# 16F1619segadc.net
KiCad netlist of a schematic drawn in EAGLE
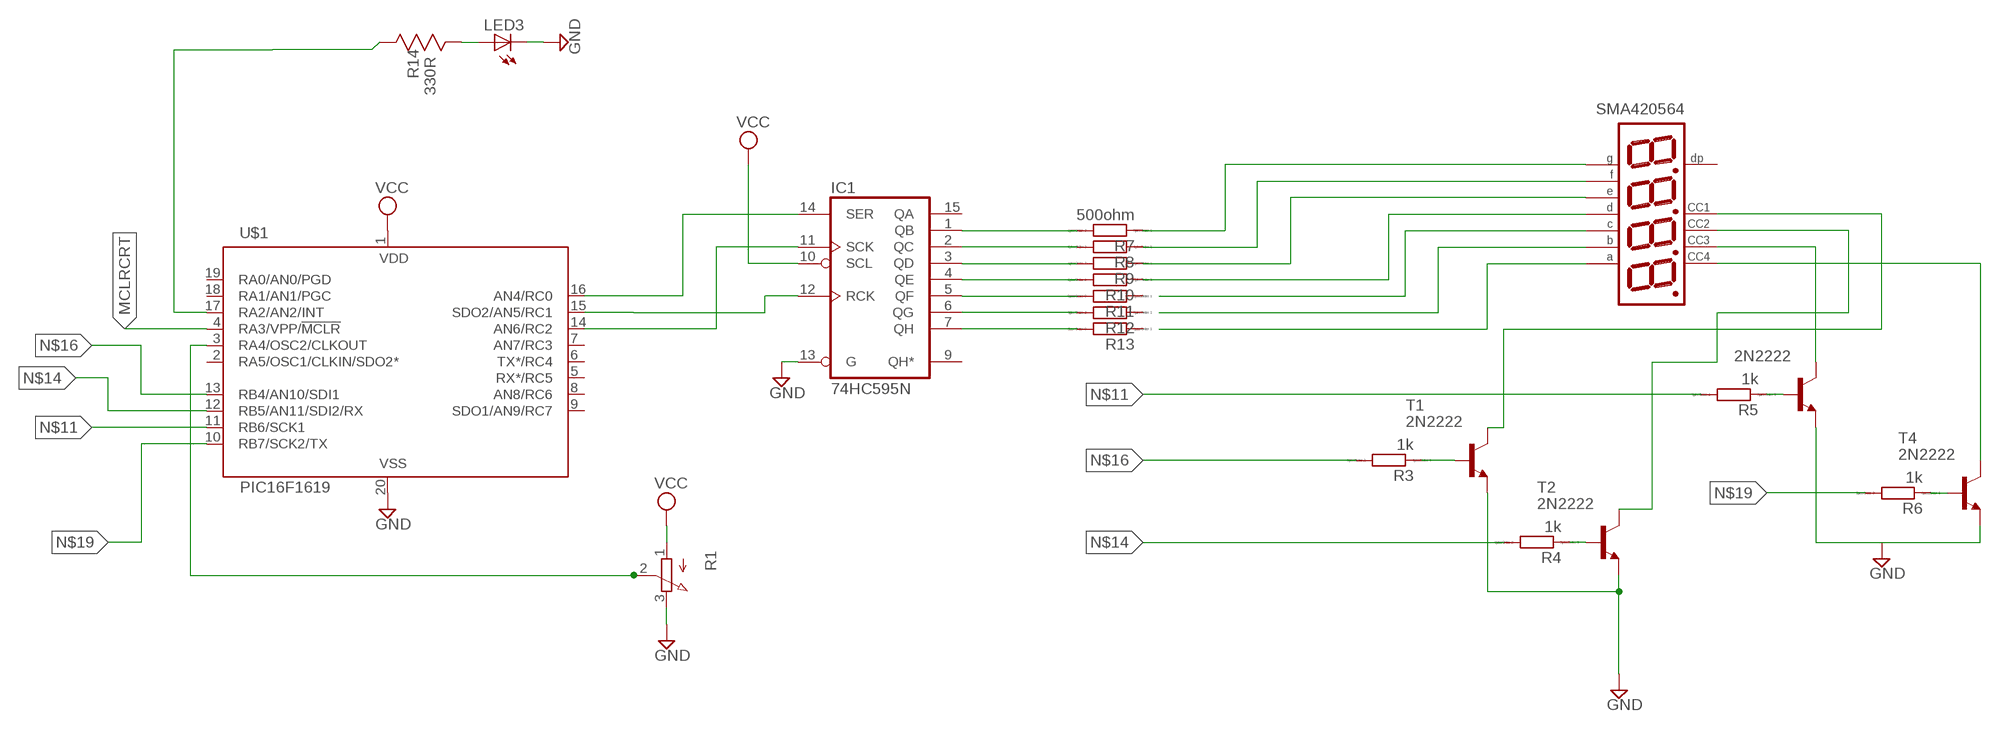
[diagram p0: schematic, sheet 1]

(export (version "E")
  (design (tool "Eeschema 10.0.6"))
  (components
    (comp (ref "IC1")
      (value "74HC595N")
      (footprint "eagle-import:DIL16")
      (libsource (lib "eagle-import") (part "74595NHC"))
    )
    (comp (ref "LED3")
      (value "LEDCHIP-LED0603")
      (footprint "eagle-import:CHIP-LED0603")
      (libsource (lib "eagle-import") (part "LEDCHIP-LED0603"))
    )
    (comp (ref "R1")
      (value "3RP/1610N")
      (footprint "eagle-import:3RP_1610N")
      (libsource (lib "eagle-import") (part "3RP/1610N"))
    )
    (comp (ref "R3")
      (value "1k")
      (footprint "eagle-import:0204_7")
      (libsource (lib "eagle-import") (part "R0204/7"))
    )
    (comp (ref "R4")
      (value "1k")
      (footprint "eagle-import:0204_7")
      (libsource (lib "eagle-import") (part "R0204/7"))
    )
    (comp (ref "R5")
      (value "1k")
      (footprint "eagle-import:0204_7")
      (libsource (lib "eagle-import") (part "R0204/7"))
    )
    (comp (ref "R6")
      (value "1k")
      (footprint "eagle-import:0204_7")
      (libsource (lib "eagle-import") (part "R0204/7"))
    )
    (comp (ref "R7")
      (value "500ohm")
      (footprint "eagle-import:0204_7")
      (libsource (lib "eagle-import") (part "R0204/7"))
    )
    (comp (ref "R8")
      (value "R0204/7")
      (footprint "eagle-import:0204_7")
      (libsource (lib "eagle-import") (part "R0204/7"))
    )
    (comp (ref "R9")
      (value "R0204/7")
      (footprint "eagle-import:0204_7")
      (libsource (lib "eagle-import") (part "R0204/7"))
    )
    (comp (ref "R10")
      (value "R0204/7")
      (footprint "eagle-import:0204_7")
      (libsource (lib "eagle-import") (part "R0204/7"))
    )
    (comp (ref "R11")
      (value "R0204/7")
      (footprint "eagle-import:0204_7")
      (libsource (lib "eagle-import") (part "R0204/7"))
    )
    (comp (ref "R12")
      (value "R0204/7")
      (footprint "eagle-import:0204_7")
      (libsource (lib "eagle-import") (part "R0204/7"))
    )
    (comp (ref "R13")
      (value "R0204/7")
      (footprint "eagle-import:0204_7")
      (libsource (lib "eagle-import") (part "R0204/7"))
    )
    (comp (ref "R14")
      (value "330R")
      (footprint "eagle-import:RESC1608X60N")
      (fields (field (name "MPN") "MC0.063W06031%330R") (field (name "TOLERANCE") "±1%"))
      (libsource (lib "eagle-import") (part "MC0.063W06031%330R"))
    )
    (comp (ref "SMA420564")
      (value "NFD-5641AS")
      (footprint "eagle-import:NFD-5641")
      (libsource (lib "eagle-import") (part "NFD-5641AS"))
    )
    (comp (ref "T1")
      (value "2N2222")
      (footprint "eagle-import:TO18")
      (libsource (lib "eagle-import") (part "2N2222"))
    )
    (comp (ref "T2")
      (value "2N2222")
      (footprint "eagle-import:TO18")
      (libsource (lib "eagle-import") (part "2N2222"))
    )
    (comp (ref "T3")
      (value "2N2222")
      (footprint "eagle-import:TO18")
      (libsource (lib "eagle-import") (part "2N2222"))
    )
    (comp (ref "T4")
      (value "2N2222")
      (footprint "eagle-import:TO18")
      (libsource (lib "eagle-import") (part "2N2222"))
    )
    (comp (ref "U$1")
      (value "PIC16F1619")
      (footprint "eagle-import:SSOP20")
      (libsource (lib "eagle-import") (part "PIC16F1829"))
    )
  )
  (nets
    (net (code "1") (name "GND") (class "Default")
      (node (ref "IC1") (pin "13") (pinfunction "G_13") (pintype "input"))
      (node (ref "LED3") (pin "C") (pinfunction "C_C") (pintype "passive"))
      (node (ref "R1") (pin "3") (pinfunction "E_3") (pintype "passive"))
      (node (ref "T1") (pin "1") (pinfunction "E_1") (pintype "passive"))
      (node (ref "T2") (pin "1") (pinfunction "E_1") (pintype "passive"))
      (node (ref "T3") (pin "1") (pinfunction "E_1") (pintype "passive"))
      (node (ref "T4") (pin "1") (pinfunction "E_1") (pintype "passive"))
      (node (ref "U$1") (pin "20") (pinfunction "VSS_20") (pintype "power_in"))
    )
    (net (code "2") (name "MCLRCRT") (class "Default")
      (node (ref "U$1") (pin "4") (pinfunction "RA3/VPP/~{MCLR}_4") (pintype "input"))
    )
    (net (code "3") (name "N$11") (class "Default")
      (node (ref "R5") (pin "2") (pinfunction "2_2") (pintype "passive"))
      (node (ref "U$1") (pin "11") (pinfunction "RB6/SCK1_11") (pintype "bidirectional"))
    )
    (net (code "4") (name "N$14") (class "Default")
      (node (ref "R4") (pin "2") (pinfunction "2_2") (pintype "passive"))
      (node (ref "U$1") (pin "12") (pinfunction "RB5/AN11/SDI2/RX_12") (pintype "bidirectional"))
    )
    (net (code "5") (name "N$16") (class "Default")
      (node (ref "R3") (pin "2") (pinfunction "2_2") (pintype "passive"))
      (node (ref "U$1") (pin "13") (pinfunction "RB4/AN10/SDI1_13") (pintype "bidirectional"))
    )
    (net (code "6") (name "N$19") (class "Default")
      (node (ref "R6") (pin "2") (pinfunction "2_2") (pintype "passive"))
      (node (ref "U$1") (pin "10") (pinfunction "RB7/SCK2/TX_10") (pintype "bidirectional"))
    )
    (net (code "7") (name "Net-(IC1A-QB)") (class "Default")
      (node (ref "IC1") (pin "1") (pinfunction "QB_1") (pintype "tri_state"))
      (node (ref "R7") (pin "2") (pinfunction "2_2") (pintype "passive"))
    )
    (net (code "8") (name "Net-(IC1A-QC)") (class "Default")
      (node (ref "IC1") (pin "2") (pinfunction "QC_2") (pintype "tri_state"))
      (node (ref "R8") (pin "2") (pinfunction "2_2") (pintype "passive"))
    )
    (net (code "9") (name "Net-(IC1A-QD)") (class "Default")
      (node (ref "IC1") (pin "3") (pinfunction "QD_3") (pintype "tri_state"))
      (node (ref "R9") (pin "2") (pinfunction "2_2") (pintype "passive"))
    )
    (net (code "10") (name "Net-(IC1A-QE)") (class "Default")
      (node (ref "IC1") (pin "4") (pinfunction "QE_4") (pintype "tri_state"))
      (node (ref "R10") (pin "2") (pinfunction "2_2") (pintype "passive"))
    )
    (net (code "11") (name "Net-(IC1A-QF)") (class "Default")
      (node (ref "IC1") (pin "5") (pinfunction "QF_5") (pintype "tri_state"))
      (node (ref "R11") (pin "2") (pinfunction "2_2") (pintype "passive"))
    )
    (net (code "12") (name "Net-(IC1A-QG)") (class "Default")
      (node (ref "IC1") (pin "6") (pinfunction "QG_6") (pintype "tri_state"))
      (node (ref "R12") (pin "2") (pinfunction "2_2") (pintype "passive"))
    )
    (net (code "13") (name "Net-(IC1A-QH)") (class "Default")
      (node (ref "IC1") (pin "7") (pinfunction "QH_7") (pintype "tri_state"))
      (node (ref "R13") (pin "2") (pinfunction "2_2") (pintype "passive"))
    )
    (net (code "14") (name "Net-(IC1A-RCK)") (class "Default")
      (node (ref "IC1") (pin "12") (pinfunction "RCK_12") (pintype "input"))
      (node (ref "U$1") (pin "15") (pinfunction "SDO2/AN5/RC1_15") (pintype "bidirectional"))
    )
    (net (code "15") (name "Net-(IC1A-SCK)") (class "Default")
      (node (ref "IC1") (pin "11") (pinfunction "SCK_11") (pintype "input"))
      (node (ref "U$1") (pin "14") (pinfunction "AN6/RC2_14") (pintype "bidirectional"))
    )
    (net (code "16") (name "Net-(IC1A-SER)") (class "Default")
      (node (ref "IC1") (pin "14") (pinfunction "SER_14") (pintype "input"))
      (node (ref "U$1") (pin "16") (pinfunction "AN4/RC0_16") (pintype "bidirectional"))
    )
    (net (code "17") (name "Net-(R1-S)") (class "Default")
      (node (ref "R1") (pin "2") (pinfunction "S_2") (pintype "passive"))
      (node (ref "U$1") (pin "3") (pinfunction "RA4/OSC2/CLKOUT_3") (pintype "bidirectional"))
    )
    (net (code "18") (name "Net-(R7-Pad1)") (class "Default")
      (node (ref "R7") (pin "1") (pinfunction "1_1") (pintype "passive"))
      (node (ref "SMA420564") (pin "P$5") (pinfunction "P$5_P$5") (pintype "bidirectional"))
    )
    (net (code "19") (name "Net-(R8-Pad1)") (class "Default")
      (node (ref "R8") (pin "1") (pinfunction "1_1") (pintype "passive"))
      (node (ref "SMA420564") (pin "P$10") (pinfunction "P$10_P$10") (pintype "bidirectional"))
    )
    (net (code "20") (name "Net-(R9-Pad1)") (class "Default")
      (node (ref "R9") (pin "1") (pinfunction "1_1") (pintype "passive"))
      (node (ref "SMA420564") (pin "P$1") (pinfunction "P$1_P$1") (pintype "bidirectional"))
    )
    (net (code "21") (name "Net-(R10-Pad1)") (class "Default")
      (node (ref "R10") (pin "1") (pinfunction "1_1") (pintype "passive"))
      (node (ref "SMA420564") (pin "P$2") (pinfunction "P$2_P$2") (pintype "bidirectional"))
    )
    (net (code "22") (name "Net-(R14-R1)") (class "Default")
      (node (ref "R14") (pin "1") (pinfunction "R1_1") (pintype "passive"))
      (node (ref "U$1") (pin "17") (pinfunction "RA2/AN2/INT_17") (pintype "bidirectional"))
    )
    (net (code "23") (name "Net-(R14-R2)") (class "Default")
      (node (ref "LED3") (pin "A") (pinfunction "A_A") (pintype "passive"))
      (node (ref "R14") (pin "2") (pinfunction "R2_2") (pintype "passive"))
    )
    (net (code "24") (name "Net-(T1-B)") (class "Default")
      (node (ref "R3") (pin "1") (pinfunction "1_1") (pintype "passive"))
      (node (ref "T1") (pin "2") (pinfunction "B_2") (pintype "passive"))
    )
    (net (code "25") (name "Net-(T1-C)") (class "Default")
      (node (ref "SMA420564") (pin "P$12") (pinfunction "P$12_P$12") (pintype "bidirectional"))
      (node (ref "T1") (pin "3") (pinfunction "C_3") (pintype "passive"))
    )
    (net (code "26") (name "Net-(T2-B)") (class "Default")
      (node (ref "R4") (pin "1") (pinfunction "1_1") (pintype "passive"))
      (node (ref "T2") (pin "2") (pinfunction "B_2") (pintype "passive"))
    )
    (net (code "27") (name "Net-(T2-C)") (class "Default")
      (node (ref "SMA420564") (pin "P$9") (pinfunction "P$9_P$9") (pintype "bidirectional"))
      (node (ref "T2") (pin "3") (pinfunction "C_3") (pintype "passive"))
    )
    (net (code "28") (name "Net-(T3-B)") (class "Default")
      (node (ref "R5") (pin "1") (pinfunction "1_1") (pintype "passive"))
      (node (ref "T3") (pin "2") (pinfunction "B_2") (pintype "passive"))
    )
    (net (code "29") (name "Net-(T3-C)") (class "Default")
      (node (ref "SMA420564") (pin "P$8") (pinfunction "P$8_P$8") (pintype "bidirectional"))
      (node (ref "T3") (pin "3") (pinfunction "C_3") (pintype "passive"))
    )
    (net (code "30") (name "Net-(T4-B)") (class "Default")
      (node (ref "R6") (pin "1") (pinfunction "1_1") (pintype "passive"))
      (node (ref "T4") (pin "2") (pinfunction "B_2") (pintype "passive"))
    )
    (net (code "31") (name "Net-(T4-C)") (class "Default")
      (node (ref "SMA420564") (pin "P$6") (pinfunction "P$6_P$6") (pintype "bidirectional"))
      (node (ref "T4") (pin "3") (pinfunction "C_3") (pintype "passive"))
    )
    (net (code "32") (name "VCC") (class "Default")
      (node (ref "IC1") (pin "10") (pinfunction "SCL_10") (pintype "input"))
      (node (ref "R1") (pin "1") (pinfunction "A_1") (pintype "passive"))
      (node (ref "U$1") (pin "1") (pinfunction "VDD_1") (pintype "power_in"))
    )
    (net (code "33") (name "unconnected-(IC1A-QA-Pad15)") (class "Default")
      (node (ref "IC1") (pin "15") (pinfunction "QA_15") (pintype "tri_state"))
    )
    (net (code "34") (name "unconnected-(IC1A-QH*-Pad9)") (class "Default")
      (node (ref "IC1") (pin "9") (pinfunction "QH*_9") (pintype "tri_state"))
    )
    (net (code "35") (name "unconnected-(R11-Pad1)") (class "Default")
      (node (ref "R11") (pin "1") (pinfunction "1_1") (pintype "passive"))
    )
    (net (code "36") (name "unconnected-(R12-Pad1)") (class "Default")
      (node (ref "R12") (pin "1") (pinfunction "1_1") (pintype "passive"))
    )
    (net (code "37") (name "unconnected-(R13-Pad1)") (class "Default")
      (node (ref "R13") (pin "1") (pinfunction "1_1") (pintype "passive"))
    )
    (net (code "38") (name "unconnected-(SMA420564-PadP$3)") (class "Default")
      (node (ref "SMA420564") (pin "P$3") (pinfunction "P$3_P$3") (pintype "bidirectional"))
    )
    (net (code "39") (name "unconnected-(SMA420564-PadP$4)") (class "Default")
      (node (ref "SMA420564") (pin "P$4") (pinfunction "P$4_P$4") (pintype "bidirectional"))
    )
    (net (code "40") (name "unconnected-(SMA420564-PadP$7)") (class "Default")
      (node (ref "SMA420564") (pin "P$7") (pinfunction "P$7_P$7") (pintype "bidirectional"))
    )
    (net (code "41") (name "unconnected-(SMA420564-PadP$11)") (class "Default")
      (node (ref "SMA420564") (pin "P$11") (pinfunction "P$11_P$11") (pintype "bidirectional"))
    )
    (net (code "42") (name "unconnected-(U$1-AN7{slash}RC3-Pad7)") (class "Default")
      (node (ref "U$1") (pin "7") (pinfunction "AN7/RC3_7") (pintype "bidirectional"))
    )
    (net (code "43") (name "unconnected-(U$1-AN8{slash}RC6-Pad8)") (class "Default")
      (node (ref "U$1") (pin "8") (pinfunction "AN8/RC6_8") (pintype "bidirectional"))
    )
    (net (code "44") (name "unconnected-(U$1-RA0{slash}AN0{slash}PGD-Pad19)") (class "Default")
      (node (ref "U$1") (pin "19") (pinfunction "RA0/AN0/PGD_19") (pintype "bidirectional"))
    )
    (net (code "45") (name "unconnected-(U$1-RA1{slash}AN1{slash}PGC-Pad18)") (class "Default")
      (node (ref "U$1") (pin "18") (pinfunction "RA1/AN1/PGC_18") (pintype "bidirectional"))
    )
    (net (code "46") (name "unconnected-(U$1-RA5{slash}OSC1{slash}CLKIN{slash}SDO2*-Pad2)") (class "Default")
      (node (ref "U$1") (pin "2") (pinfunction "RA5/OSC1/CLKIN/SDO2*_2") (pintype "bidirectional"))
    )
    (net (code "47") (name "unconnected-(U$1-RX*{slash}RC5-Pad5)") (class "Default")
      (node (ref "U$1") (pin "5") (pinfunction "RX*/RC5_5") (pintype "bidirectional"))
    )
    (net (code "48") (name "unconnected-(U$1-SDO1{slash}AN9{slash}RC7-Pad9)") (class "Default")
      (node (ref "U$1") (pin "9") (pinfunction "SDO1/AN9/RC7_9") (pintype "bidirectional"))
    )
    (net (code "49") (name "unconnected-(U$1-TX*{slash}RC4-Pad6)") (class "Default")
      (node (ref "U$1") (pin "6") (pinfunction "TX*/RC4_6") (pintype "bidirectional"))
    )
  )
)
